# tamatebako.net
KiCad netlist of a schematic drawn in EAGLE
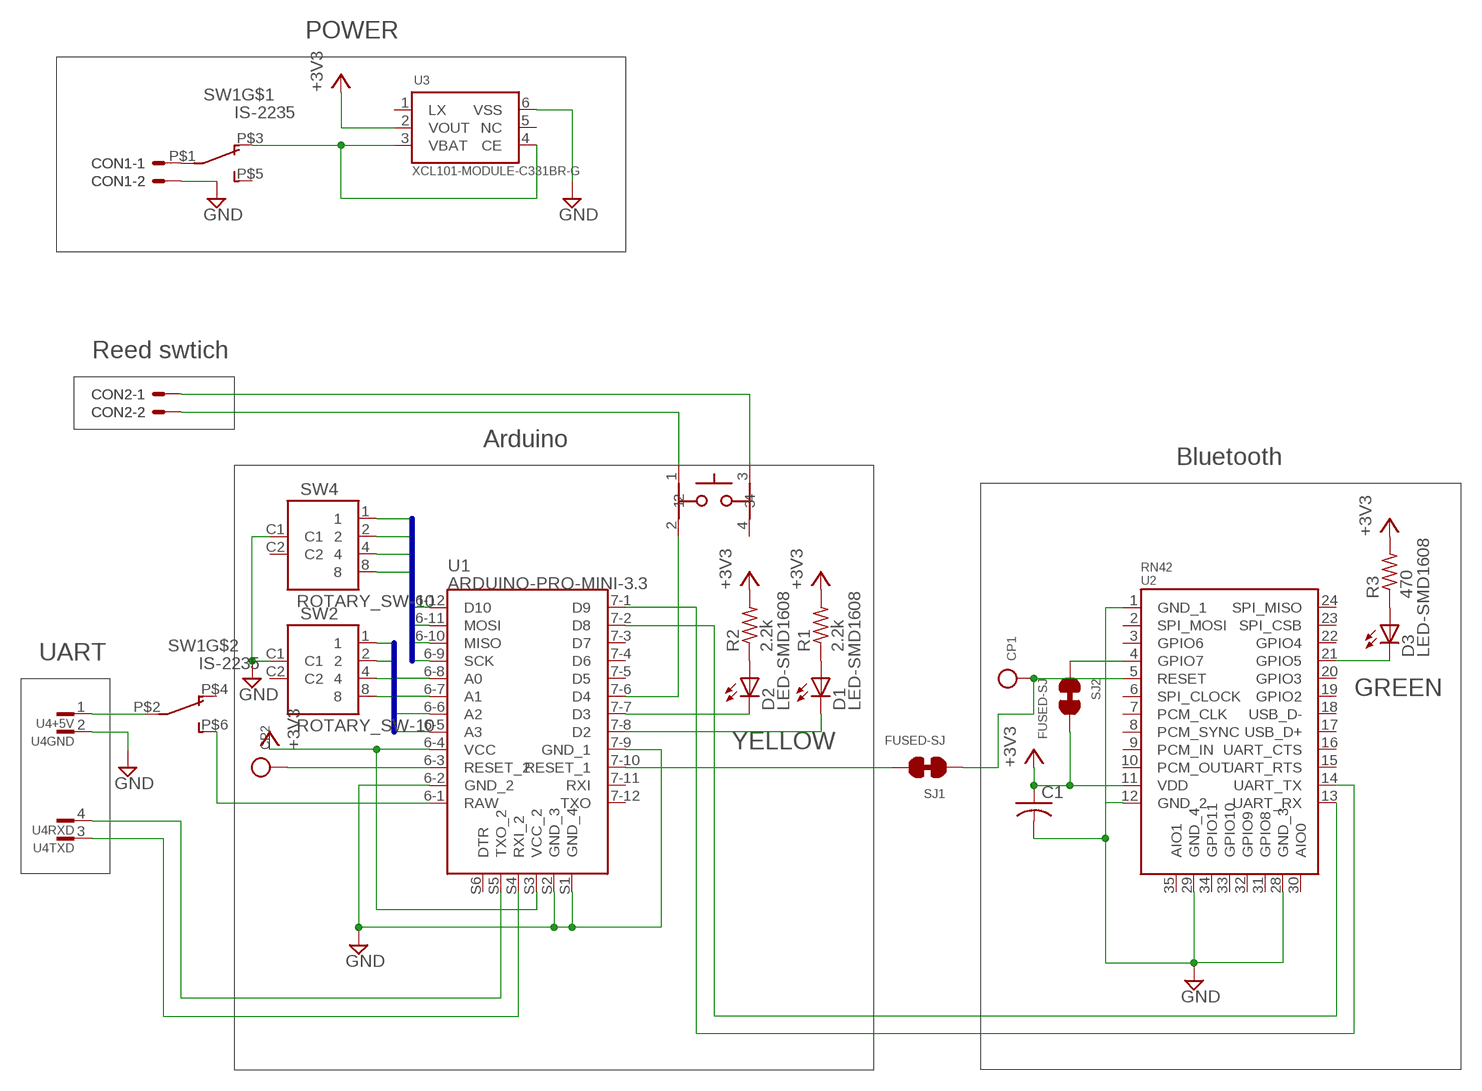
[diagram p0: schematic, sheet 1]

(export (version "E")
  (design (tool "Eeschema 10.0.6"))
  (components
    (comp (ref "C1")
      (value "C-2012")
      (footprint "eagle-import:2012-C")
      (libsource (lib "eagle-import") (part "C-2012"))
    )
    (comp (ref "CON1")
      (value "PH_CONNECTOR_2PIN")
      (footprint "eagle-import:PH_CONNECTOR_2PIN")
      (libsource (lib "eagle-import") (part "PH_CONNECTOR_2PIN"))
    )
    (comp (ref "CON2")
      (value "PH_CONNECTOR_2PIN")
      (footprint "eagle-import:PH_CONNECTOR_2PIN")
      (libsource (lib "eagle-import") (part "PH_CONNECTOR_2PIN"))
    )
    (comp (ref "CP1")
      (value "SST-1-2")
      (footprint "eagle-import:SST-1-2")
      (libsource (lib "eagle-import") (part "SST-1-2"))
    )
    (comp (ref "CP2")
      (value "SST-1-2")
      (footprint "eagle-import:SST-1-2")
      (libsource (lib "eagle-import") (part "SST-1-2"))
    )
    (comp (ref "D1")
      (value "LED-SMD1608")
      (footprint "eagle-import:D1608")
      (libsource (lib "eagle-import") (part "LED-SMD1608"))
    )
    (comp (ref "D2")
      (value "LED-SMD1608")
      (footprint "eagle-import:D1608")
      (libsource (lib "eagle-import") (part "LED-SMD1608"))
    )
    (comp (ref "D3")
      (value "LED-SMD1608")
      (footprint "eagle-import:D1608")
      (libsource (lib "eagle-import") (part "LED-SMD1608"))
    )
    (comp (ref "R1")
      (value "2.2k")
      (footprint "eagle-import:2012-R")
      (libsource (lib "eagle-import") (part "R-2012"))
    )
    (comp (ref "R2")
      (value "2.2k")
      (footprint "eagle-import:2012-R")
      (libsource (lib "eagle-import") (part "R-2012"))
    )
    (comp (ref "R3")
      (value "470")
      (footprint "eagle-import:2012-R")
      (libsource (lib "eagle-import") (part "R-2012"))
    )
    (comp (ref "SJ1")
      (value "FUSED-SJ")
      (footprint "eagle-import:FUSED-SJ")
      (libsource (lib "eagle-import") (part "FUSED-SJ"))
    )
    (comp (ref "SJ2")
      (value "FUSED-SJ")
      (footprint "eagle-import:FUSED-SJ")
      (libsource (lib "eagle-import") (part "FUSED-SJ"))
    )
    (comp (ref "SW1")
      (value "IS-2235")
      (footprint "eagle-import:IS-2235")
      (libsource (lib "eagle-import") (part "IS-2235"))
    )
    (comp (ref "SW2")
      (value "ROTARY_SW-10")
      (footprint "eagle-import:ROTARY_SW")
      (libsource (lib "eagle-import") (part "ROTARY_SW-10"))
    )
    (comp (ref "SW3")
      (value "PUSHSW")
      (footprint "eagle-import:PUSHSW")
      (libsource (lib "eagle-import") (part "PUSHSW"))
    )
    (comp (ref "SW4")
      (value "ROTARY_SW-10")
      (footprint "eagle-import:ROTARY_SW")
      (libsource (lib "eagle-import") (part "ROTARY_SW-10"))
    )
    (comp (ref "U1")
      (value "ARDUINO-PRO-MINI-3.3")
      (footprint "eagle-import:ARDUINO_PRO_MINI")
      (libsource (lib "eagle-import") (part "ARDUINO-PRO-MINI-3.3"))
    )
    (comp (ref "U2")
      (value "RN42")
      (footprint "eagle-import:RN42")
      (libsource (lib "eagle-import") (part "RN42"))
    )
    (comp (ref "U3")
      (value "XCL101-MODULE-C331BR-G")
      (footprint "eagle-import:XCL101-MODULE")
      (libsource (lib "eagle-import") (part "XCL101-MODULE-C331BR-G"))
    )
    (comp (ref "U4")
      (value "UART_MODULE")
      (footprint "eagle-import:MICRO_USB_SERIAL_MODULE")
      (libsource (lib "eagle-import") (part "UART_MODULE"))
    )
  )
  (nets
    (net (code "1") (name "+3V3") (class "Default")
      (node (ref "C1") (pin "1") (pinfunction "1_1") (pintype "passive"))
      (node (ref "R1") (pin "2") (pinfunction "2_2") (pintype "passive"))
      (node (ref "R2") (pin "2") (pinfunction "2_2") (pintype "passive"))
      (node (ref "R3") (pin "2") (pinfunction "2_2") (pintype "passive"))
      (node (ref "SJ2") (pin "2") (pinfunction "P$2_2") (pintype "bidirectional"))
      (node (ref "U1") (pin "6-4") (pinfunction "VCC_6-4") (pintype "bidirectional"))
      (node (ref "U1") (pin "S3") (pinfunction "VCC_2_S3") (pintype "bidirectional"))
      (node (ref "U2") (pin "11") (pinfunction "VDD_11") (pintype "bidirectional"))
      (node (ref "U3") (pin "2") (pinfunction "VOUT_2") (pintype "bidirectional"))
    )
    (net (code "2") (name "/LOWER0") (class "Default")
      (node (ref "SW2") (pin "1") (pinfunction "1_1") (pintype "bidirectional"))
      (node (ref "U1") (pin "6-8") (pinfunction "A0_6-8") (pintype "bidirectional"))
    )
    (net (code "3") (name "/LOWER1") (class "Default")
      (node (ref "SW2") (pin "2") (pinfunction "2_2") (pintype "bidirectional"))
      (node (ref "U1") (pin "6-7") (pinfunction "A1_6-7") (pintype "bidirectional"))
    )
    (net (code "4") (name "/LOWER2") (class "Default")
      (node (ref "SW2") (pin "4") (pinfunction "4_4") (pintype "bidirectional"))
      (node (ref "U1") (pin "6-6") (pinfunction "A2_6-6") (pintype "bidirectional"))
    )
    (net (code "5") (name "/LOWER3") (class "Default")
      (node (ref "SW2") (pin "8") (pinfunction "8_8") (pintype "bidirectional"))
      (node (ref "U1") (pin "6-5") (pinfunction "A3_6-5") (pintype "bidirectional"))
    )
    (net (code "6") (name "/UPPER0") (class "Default")
      (node (ref "SW4") (pin "1") (pinfunction "1_1") (pintype "bidirectional"))
      (node (ref "U1") (pin "6-12") (pinfunction "D10_6-12") (pintype "bidirectional"))
    )
    (net (code "7") (name "/UPPER1") (class "Default")
      (node (ref "SW4") (pin "2") (pinfunction "2_2") (pintype "bidirectional"))
      (node (ref "U1") (pin "6-11") (pinfunction "MOSI_6-11") (pintype "bidirectional"))
    )
    (net (code "8") (name "/UPPER2") (class "Default")
      (node (ref "SW4") (pin "4") (pinfunction "4_4") (pintype "bidirectional"))
      (node (ref "U1") (pin "6-10") (pinfunction "MISO_6-10") (pintype "bidirectional"))
    )
    (net (code "9") (name "/UPPER3") (class "Default")
      (node (ref "SW4") (pin "8") (pinfunction "8_8") (pintype "bidirectional"))
      (node (ref "U1") (pin "6-9") (pinfunction "SCK_6-9") (pintype "bidirectional"))
    )
    (net (code "10") (name "GND") (class "Default")
      (node (ref "C1") (pin "2") (pinfunction "2_2") (pintype "passive"))
      (node (ref "CON1") (pin "2") (pinfunction "S_2") (pintype "passive"))
      (node (ref "SW2") (pin "C1") (pinfunction "C1_C1") (pintype "bidirectional"))
      (node (ref "SW4") (pin "C1") (pinfunction "C1_C1") (pintype "bidirectional"))
      (node (ref "U1") (pin "6-2") (pinfunction "GND_2_6-2") (pintype "bidirectional"))
      (node (ref "U1") (pin "7-9") (pinfunction "GND_1_7-9") (pintype "bidirectional"))
      (node (ref "U1") (pin "S1") (pinfunction "GND_4_S1") (pintype "bidirectional"))
      (node (ref "U1") (pin "S2") (pinfunction "GND_3_S2") (pintype "bidirectional"))
      (node (ref "U2") (pin "1") (pinfunction "GND_1_1") (pintype "bidirectional"))
      (node (ref "U2") (pin "12") (pinfunction "GND_2_12") (pintype "bidirectional"))
      (node (ref "U2") (pin "28") (pinfunction "GND_3_28") (pintype "bidirectional"))
      (node (ref "U2") (pin "29") (pinfunction "GND_4_29") (pintype "bidirectional"))
      (node (ref "U3") (pin "6") (pinfunction "VSS_6") (pintype "bidirectional"))
      (node (ref "U4") (pin "2") (pinfunction "P$1_2") (pintype "bidirectional"))
    )
    (net (code "11") (name "Net-(CON1A-S)") (class "Default")
      (node (ref "CON1") (pin "1") (pinfunction "S_1") (pintype "passive"))
      (node (ref "SW1") (pin "P$1") (pinfunction "P_P$1") (pintype "passive"))
    )
    (net (code "12") (name "Net-(CON2A-S)") (class "Default")
      (node (ref "CON2") (pin "1") (pinfunction "S_1") (pintype "passive"))
      (node (ref "SW3") (pin "3") (pinfunction "3_3") (pintype "bidirectional"))
    )
    (net (code "13") (name "Net-(CON2B-S)") (class "Default")
      (node (ref "CON2") (pin "2") (pinfunction "S_2") (pintype "passive"))
      (node (ref "SW3") (pin "1") (pinfunction "1_1") (pintype "bidirectional"))
    )
    (net (code "14") (name "Net-(CP1-SIGNAL)") (class "Default")
      (node (ref "CP1") (pin "1") (pinfunction "SIGNAL_1") (pintype "bidirectional"))
      (node (ref "SJ1") (pin "1") (pinfunction "P$1_1") (pintype "bidirectional"))
      (node (ref "U2") (pin "5") (pinfunction "RESET_5") (pintype "bidirectional"))
    )
    (net (code "15") (name "Net-(CP2-SIGNAL)") (class "Default")
      (node (ref "CP2") (pin "1") (pinfunction "SIGNAL_1") (pintype "bidirectional"))
      (node (ref "U1") (pin "6-3") (pinfunction "RESET_2_6-3") (pintype "bidirectional"))
    )
    (net (code "16") (name "Net-(D1-PadA)") (class "Default")
      (node (ref "D1") (pin "A") (pinfunction "A_A") (pintype "passive"))
      (node (ref "R1") (pin "1") (pinfunction "1_1") (pintype "passive"))
    )
    (net (code "17") (name "Net-(D2-PadA)") (class "Default")
      (node (ref "D2") (pin "A") (pinfunction "A_A") (pintype "passive"))
      (node (ref "R2") (pin "1") (pinfunction "1_1") (pintype "passive"))
    )
    (net (code "18") (name "Net-(D3-PadA)") (class "Default")
      (node (ref "D3") (pin "A") (pinfunction "A_A") (pintype "passive"))
      (node (ref "R3") (pin "1") (pinfunction "1_1") (pintype "passive"))
    )
    (net (code "19") (name "Net-(SJ1-P$2)") (class "Default")
      (node (ref "SJ1") (pin "2") (pinfunction "P$2_2") (pintype "bidirectional"))
      (node (ref "U1") (pin "7-10") (pinfunction "RESET_1_7-10") (pintype "bidirectional"))
    )
    (net (code "20") (name "Net-(SJ2-P$1)") (class "Default")
      (node (ref "SJ2") (pin "1") (pinfunction "P$1_1") (pintype "bidirectional"))
      (node (ref "U2") (pin "4") (pinfunction "GPIO7_4") (pintype "bidirectional"))
    )
    (net (code "21") (name "Net-(SW1A-O)") (class "Default")
      (node (ref "SW1") (pin "P$3") (pinfunction "O_P$3") (pintype "passive"))
      (node (ref "U3") (pin "3") (pinfunction "VBAT_3") (pintype "bidirectional"))
      (node (ref "U3") (pin "4") (pinfunction "CE_4") (pintype "bidirectional"))
    )
    (net (code "22") (name "Net-(SW1B-P)") (class "Default")
      (node (ref "SW1") (pin "P$2") (pinfunction "P_P$2") (pintype "passive"))
      (node (ref "U4") (pin "1") (pinfunction "P$1_1") (pintype "bidirectional"))
    )
    (net (code "23") (name "Net-(SW1B-S)") (class "Default")
      (node (ref "SW1") (pin "P$6") (pinfunction "S_P$6") (pintype "passive"))
      (node (ref "U1") (pin "6-1") (pinfunction "RAW_6-1") (pintype "bidirectional"))
    )
    (net (code "24") (name "Net-(U1-D2)") (class "Default")
      (node (ref "D1") (pin "K") (pinfunction "K_K") (pintype "passive"))
      (node (ref "U1") (pin "7-8") (pinfunction "D2_7-8") (pintype "bidirectional"))
    )
    (net (code "25") (name "Net-(U1-D3)") (class "Default")
      (node (ref "D2") (pin "K") (pinfunction "K_K") (pintype "passive"))
      (node (ref "U1") (pin "7-7") (pinfunction "D3_7-7") (pintype "bidirectional"))
    )
    (net (code "26") (name "Net-(U1-D4)") (class "Default")
      (node (ref "SW3") (pin "2") (pinfunction "2_2") (pintype "bidirectional"))
      (node (ref "U1") (pin "7-6") (pinfunction "D4_7-6") (pintype "bidirectional"))
    )
    (net (code "27") (name "Net-(U1-D8)") (class "Default")
      (node (ref "U1") (pin "7-2") (pinfunction "D8_7-2") (pintype "bidirectional"))
      (node (ref "U2") (pin "13") (pinfunction "UART_RX_13") (pintype "bidirectional"))
    )
    (net (code "28") (name "Net-(U1-D9)") (class "Default")
      (node (ref "U1") (pin "7-1") (pinfunction "D9_7-1") (pintype "bidirectional"))
      (node (ref "U2") (pin "14") (pinfunction "UART_TX_14") (pintype "bidirectional"))
    )
    (net (code "29") (name "Net-(U1-RXI_2)") (class "Default")
      (node (ref "U1") (pin "S4") (pinfunction "RXI_2_S4") (pintype "bidirectional"))
      (node (ref "U4") (pin "3") (pinfunction "P$1_3") (pintype "bidirectional"))
    )
    (net (code "30") (name "Net-(U1-TXO_2)") (class "Default")
      (node (ref "U1") (pin "S5") (pinfunction "TXO_2_S5") (pintype "bidirectional"))
      (node (ref "U4") (pin "4") (pinfunction "P$1_4") (pintype "bidirectional"))
    )
    (net (code "31") (name "Net-(U2-GPIO5)") (class "Default")
      (node (ref "D3") (pin "K") (pinfunction "K_K") (pintype "passive"))
      (node (ref "U2") (pin "21") (pinfunction "GPIO5_21") (pintype "bidirectional"))
    )
    (net (code "32") (name "unconnected-(SW1A-S-PadP$5)") (class "Default")
      (node (ref "SW1") (pin "P$5") (pinfunction "S_P$5") (pintype "passive"))
    )
    (net (code "33") (name "unconnected-(SW1B-O-PadP$4)") (class "Default")
      (node (ref "SW1") (pin "P$4") (pinfunction "O_P$4") (pintype "passive"))
    )
    (net (code "34") (name "unconnected-(SW2-PadC2)") (class "Default")
      (node (ref "SW2") (pin "C2") (pinfunction "C2_C2") (pintype "bidirectional"))
    )
    (net (code "35") (name "unconnected-(SW3-Pad4)") (class "Default")
      (node (ref "SW3") (pin "4") (pinfunction "4_4") (pintype "bidirectional"))
    )
    (net (code "36") (name "unconnected-(SW4-PadC2)") (class "Default")
      (node (ref "SW4") (pin "C2") (pinfunction "C2_C2") (pintype "bidirectional"))
    )
    (net (code "37") (name "unconnected-(U1-D5-Pad7-5)") (class "Default")
      (node (ref "U1") (pin "7-5") (pinfunction "D5_7-5") (pintype "bidirectional"))
    )
    (net (code "38") (name "unconnected-(U1-D6-Pad7-4)") (class "Default")
      (node (ref "U1") (pin "7-4") (pinfunction "D6_7-4") (pintype "bidirectional"))
    )
    (net (code "39") (name "unconnected-(U1-D7-Pad7-3)") (class "Default")
      (node (ref "U1") (pin "7-3") (pinfunction "D7_7-3") (pintype "bidirectional"))
    )
    (net (code "40") (name "unconnected-(U1-DTR-PadS6)") (class "Default")
      (node (ref "U1") (pin "S6") (pinfunction "DTR_S6") (pintype "bidirectional"))
    )
    (net (code "41") (name "unconnected-(U1-RXI-Pad7-11)") (class "Default")
      (node (ref "U1") (pin "7-11") (pinfunction "RXI_7-11") (pintype "bidirectional"))
    )
    (net (code "42") (name "unconnected-(U1-TXO-Pad7-12)") (class "Default")
      (node (ref "U1") (pin "7-12") (pinfunction "TXO_7-12") (pintype "bidirectional"))
    )
    (net (code "43") (name "unconnected-(U2-AIO0-Pad30)") (class "Default")
      (node (ref "U2") (pin "30") (pinfunction "AIO0_30") (pintype "bidirectional"))
    )
    (net (code "44") (name "unconnected-(U2-AIO1-Pad35)") (class "Default")
      (node (ref "U2") (pin "35") (pinfunction "AIO1_35") (pintype "bidirectional"))
    )
    (net (code "45") (name "unconnected-(U2-GPIO2-Pad19)") (class "Default")
      (node (ref "U2") (pin "19") (pinfunction "GPIO2_19") (pintype "bidirectional"))
    )
    (net (code "46") (name "unconnected-(U2-GPIO3-Pad20)") (class "Default")
      (node (ref "U2") (pin "20") (pinfunction "GPIO3_20") (pintype "bidirectional"))
    )
    (net (code "47") (name "unconnected-(U2-GPIO4-Pad22)") (class "Default")
      (node (ref "U2") (pin "22") (pinfunction "GPIO4_22") (pintype "bidirectional"))
    )
    (net (code "48") (name "unconnected-(U2-GPIO6-Pad3)") (class "Default")
      (node (ref "U2") (pin "3") (pinfunction "GPIO6_3") (pintype "bidirectional"))
    )
    (net (code "49") (name "unconnected-(U2-GPIO8-Pad31)") (class "Default")
      (node (ref "U2") (pin "31") (pinfunction "GPIO8_31") (pintype "bidirectional"))
    )
    (net (code "50") (name "unconnected-(U2-GPIO9-Pad32)") (class "Default")
      (node (ref "U2") (pin "32") (pinfunction "GPIO9_32") (pintype "bidirectional"))
    )
    (net (code "51") (name "unconnected-(U2-GPIO10-Pad33)") (class "Default")
      (node (ref "U2") (pin "33") (pinfunction "GPIO10_33") (pintype "bidirectional"))
    )
    (net (code "52") (name "unconnected-(U2-GPIO11-Pad34)") (class "Default")
      (node (ref "U2") (pin "34") (pinfunction "GPIO11_34") (pintype "bidirectional"))
    )
    (net (code "53") (name "unconnected-(U2-PCM_CLK-Pad7)") (class "Default")
      (node (ref "U2") (pin "7") (pinfunction "PCM_CLK_7") (pintype "bidirectional"))
    )
    (net (code "54") (name "unconnected-(U2-PCM_IN-Pad9)") (class "Default")
      (node (ref "U2") (pin "9") (pinfunction "PCM_IN_9") (pintype "bidirectional"))
    )
    (net (code "55") (name "unconnected-(U2-PCM_OUT-Pad10)") (class "Default")
      (node (ref "U2") (pin "10") (pinfunction "PCM_OUT_10") (pintype "bidirectional"))
    )
    (net (code "56") (name "unconnected-(U2-PCM_SYNC-Pad8)") (class "Default")
      (node (ref "U2") (pin "8") (pinfunction "PCM_SYNC_8") (pintype "bidirectional"))
    )
    (net (code "57") (name "unconnected-(U2-SPI_CLOCK-Pad6)") (class "Default")
      (node (ref "U2") (pin "6") (pinfunction "SPI_CLOCK_6") (pintype "bidirectional"))
    )
    (net (code "58") (name "unconnected-(U2-SPI_CSB-Pad23)") (class "Default")
      (node (ref "U2") (pin "23") (pinfunction "SPI_CSB_23") (pintype "bidirectional"))
    )
    (net (code "59") (name "unconnected-(U2-SPI_MISO-Pad24)") (class "Default")
      (node (ref "U2") (pin "24") (pinfunction "SPI_MISO_24") (pintype "bidirectional"))
    )
    (net (code "60") (name "unconnected-(U2-SPI_MOSI-Pad2)") (class "Default")
      (node (ref "U2") (pin "2") (pinfunction "SPI_MOSI_2") (pintype "bidirectional"))
    )
    (net (code "61") (name "unconnected-(U2-UART_CTS-Pad16)") (class "Default")
      (node (ref "U2") (pin "16") (pinfunction "UART_CTS_16") (pintype "bidirectional"))
    )
    (net (code "62") (name "unconnected-(U2-UART_RTS-Pad15)") (class "Default")
      (node (ref "U2") (pin "15") (pinfunction "UART_RTS_15") (pintype "bidirectional"))
    )
    (net (code "63") (name "unconnected-(U2-USB_D+-Pad17)") (class "Default")
      (node (ref "U2") (pin "17") (pinfunction "USB_D+_17") (pintype "bidirectional"))
    )
    (net (code "64") (name "unconnected-(U2-USB_D--Pad18)") (class "Default")
      (node (ref "U2") (pin "18") (pinfunction "USB_D-_18") (pintype "bidirectional"))
    )
    (net (code "65") (name "unconnected-(U3-LX-Pad1)") (class "Default")
      (node (ref "U3") (pin "1") (pinfunction "LX_1") (pintype "bidirectional"))
    )
    (net (code "66") (name "unconnected-(U3-NC-Pad5)") (class "Default")
      (node (ref "U3") (pin "5") (pinfunction "NC_5") (pintype "bidirectional"))
    )
  )
)
